# Schematic_EASYEDA.net
KiCad netlist of a schematic drawn in EasyEDA
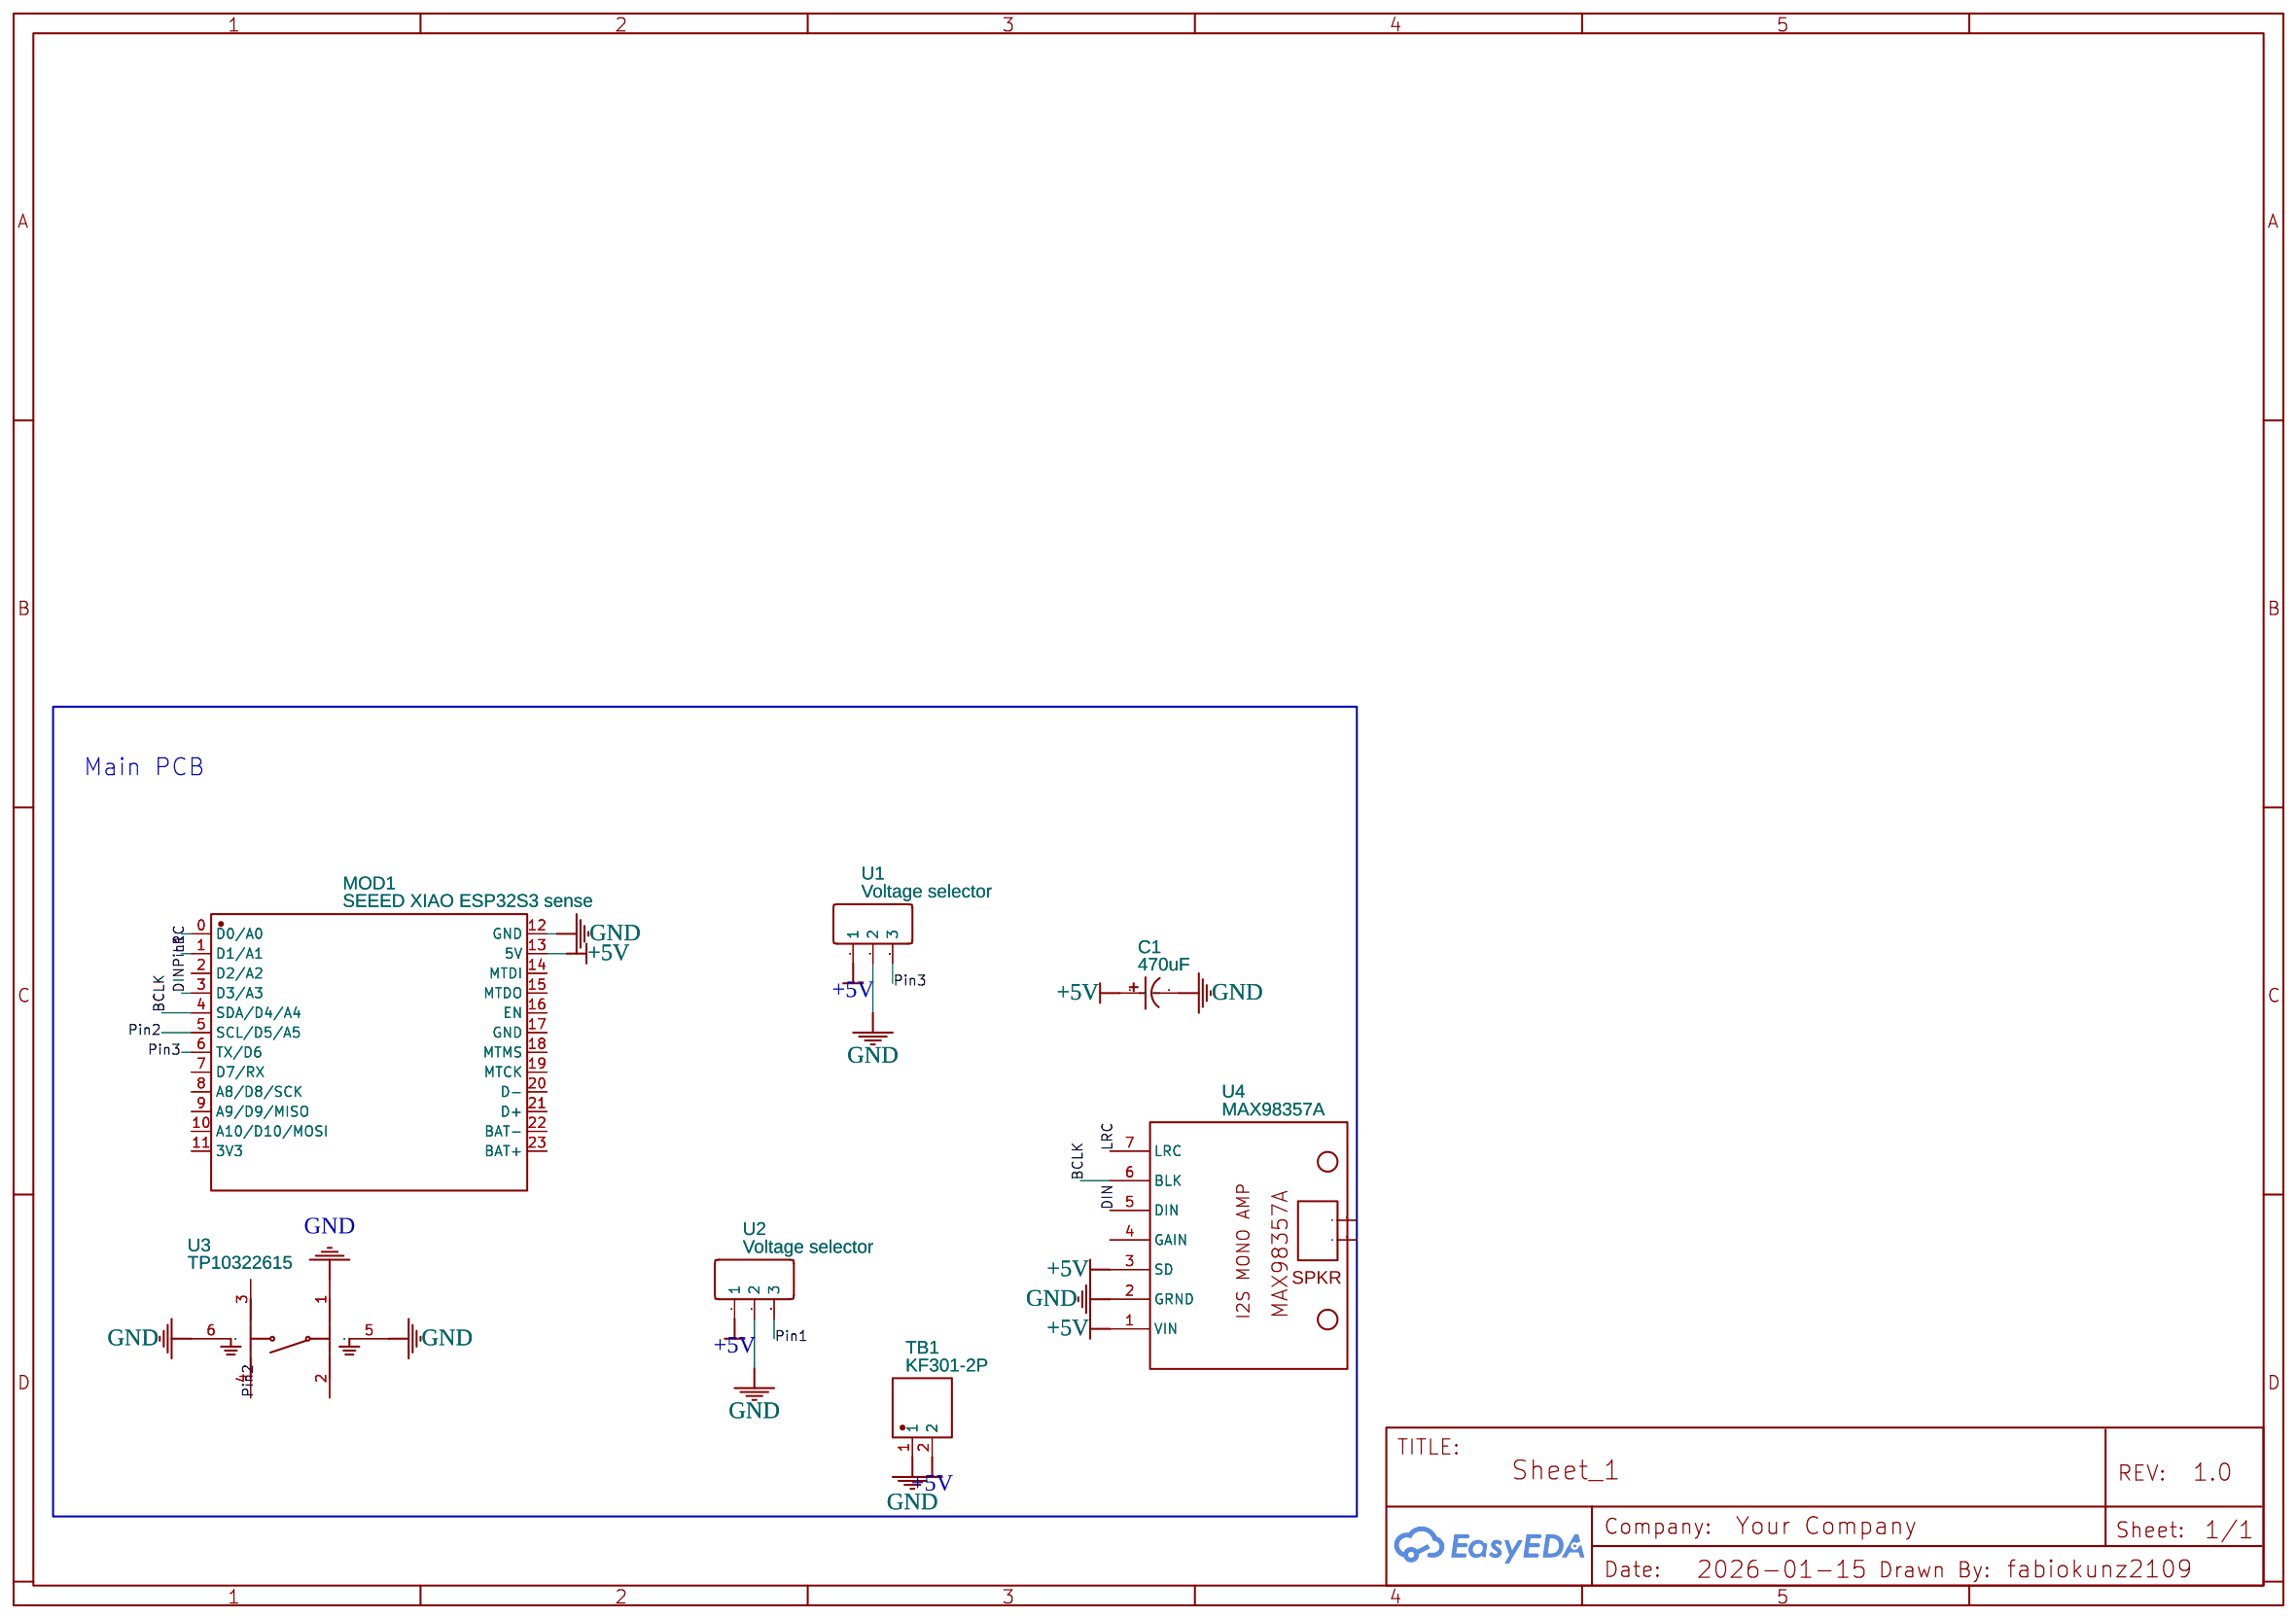
[diagram p0: schematic sheet]

(export (version "E")
  (design (tool "Eeschema 10.0.6"))
  (components
    (comp (ref "C1") (value "470uF") (libsource (lib "") (part "470uF 10V Flat 6.3x12")))
    (comp (ref "MOD1")
      (value "SEEED XIAO ESP32S3 sense")
      (libsource (lib "") (part "SEEED XIAO ESP32S3 sense"))
    )
    (comp (ref "TB1") (value "KF301-2P") (libsource (lib "") (part "KF301-2P")))
    (comp (ref "U1") (value "Voltage selector") (libsource (lib "") (part "Header-Male-2.54-1x3-2-1-Jumper")))
    (comp (ref "U2") (value "Voltage selector") (libsource (lib "") (part "Header-Male-2.54-1x3-2-1-Jumper")))
    (comp (ref "U3")
      (value "TP10322615")
      (fields (field (name "Manufacturer") "ROCPU Switches(台普)"))
      (libsource (lib "") (part "TP10322615"))
    )
    (comp (ref "U4") (value "MAX98357A") (libsource (lib "") (part "MAX98357A COPY")))
  )
  (nets
    (net (code "1") (name "+5V") (class "Default")
      (node (ref "C1") (pin "1") (pinfunction "1_1") (pintype "input"))
      (node (ref "MOD1") (pin "13") (pinfunction "5V_13") (pintype "unspecified"))
      (node (ref "TB1") (pin "2") (pinfunction "2_2") (pintype "unspecified"))
      (node (ref "U1") (pin "1") (pinfunction "1_1") (pintype "unspecified"))
      (node (ref "U2") (pin "1") (pinfunction "1_1") (pintype "unspecified"))
      (node (ref "U4") (pin "1") (pinfunction "VIN_1") (pintype "unspecified"))
      (node (ref "U4") (pin "3") (pinfunction "SD_3") (pintype "unspecified"))
    )
    (net (code "2") (name "/BCLK") (class "Default")
      (node (ref "MOD1") (pin "4") (pinfunction "SDA/D4/A4_4") (pintype "unspecified"))
      (node (ref "U4") (pin "6") (pinfunction "BLK_6") (pintype "unspecified"))
    )
    (net (code "3") (name "/DIN") (class "Default")
      (node (ref "MOD1") (pin "3") (pinfunction "D3/A3_3") (pintype "unspecified"))
      (node (ref "U4") (pin "5") (pinfunction "DIN_5") (pintype "unspecified"))
    )
    (net (code "4") (name "/LRC") (class "Default")
      (node (ref "MOD1") (pin "1") (pinfunction "D1/A1_1") (pintype "unspecified"))
      (node (ref "U4") (pin "7") (pinfunction "LRC_7") (pintype "unspecified"))
    )
    (net (code "5") (name "/Pin1") (class "Default")
      (node (ref "MOD1") (pin "0") (pinfunction "D0/A0_0") (pintype "unspecified"))
      (node (ref "U2") (pin "3") (pinfunction "3_3") (pintype "unspecified"))
    )
    (net (code "6") (name "/Pin2") (class "Default")
      (node (ref "MOD1") (pin "5") (pinfunction "SCL/D5/A5_5") (pintype "unspecified"))
      (node (ref "U3") (pin "4") (pinfunction "4_4") (pintype "unspecified"))
    )
    (net (code "7") (name "/Pin3") (class "Default")
      (node (ref "MOD1") (pin "6") (pinfunction "TX/D6_6") (pintype "unspecified"))
      (node (ref "U1") (pin "3") (pinfunction "3_3") (pintype "unspecified"))
    )
    (net (code "8") (name "GND") (class "Default")
      (node (ref "C1") (pin "2") (pinfunction "2_2") (pintype "input"))
      (node (ref "MOD1") (pin "12") (pinfunction "GND_12") (pintype "unspecified"))
      (node (ref "TB1") (pin "1") (pinfunction "1_1") (pintype "unspecified"))
      (node (ref "U1") (pin "2") (pinfunction "2_2") (pintype "unspecified"))
      (node (ref "U2") (pin "2") (pinfunction "2_2") (pintype "unspecified"))
      (node (ref "U3") (pin "1") (pinfunction "1_1") (pintype "unspecified"))
      (node (ref "U3") (pin "5") (pinfunction "5_5") (pintype "unspecified"))
      (node (ref "U3") (pin "6") (pinfunction "6_6") (pintype "unspecified"))
      (node (ref "U4") (pin "2") (pinfunction "GRND_2") (pintype "unspecified"))
    )
    (net (code "9") (name "unconnected-(MOD1-3V3-Pad11)") (class "Default")
      (node (ref "MOD1") (pin "11") (pinfunction "3V3_11") (pintype "unspecified"))
    )
    (net (code "10") (name "unconnected-(MOD1-A8{slash}D8{slash}SCK-Pad8)") (class "Default")
      (node (ref "MOD1") (pin "8") (pinfunction "A8/D8/SCK_8") (pintype "unspecified"))
    )
    (net (code "11") (name "unconnected-(MOD1-A9{slash}D9{slash}MISO-Pad9)") (class "Default")
      (node (ref "MOD1") (pin "9") (pinfunction "A9/D9/MISO_9") (pintype "unspecified"))
    )
    (net (code "12") (name "unconnected-(MOD1-A10{slash}D10{slash}MOSI-Pad10)") (class "Default")
      (node (ref "MOD1") (pin "10") (pinfunction "A10/D10/MOSI_10") (pintype "unspecified"))
    )
    (net (code "13") (name "unconnected-(MOD1-BAT+-Pad23)") (class "Default")
      (node (ref "MOD1") (pin "23") (pinfunction "BAT+_23") (pintype "unspecified"))
    )
    (net (code "14") (name "unconnected-(MOD1-BAT--Pad22)") (class "Default")
      (node (ref "MOD1") (pin "22") (pinfunction "BAT-_22") (pintype "unspecified"))
    )
    (net (code "15") (name "unconnected-(MOD1-D+-Pad21)") (class "Default")
      (node (ref "MOD1") (pin "21") (pinfunction "D+_21") (pintype "unspecified"))
    )
    (net (code "16") (name "unconnected-(MOD1-D--Pad20)") (class "Default")
      (node (ref "MOD1") (pin "20") (pinfunction "D-_20") (pintype "unspecified"))
    )
    (net (code "17") (name "unconnected-(MOD1-D2{slash}A2-Pad2)") (class "Default")
      (node (ref "MOD1") (pin "2") (pinfunction "D2/A2_2") (pintype "unspecified"))
    )
    (net (code "18") (name "unconnected-(MOD1-D7{slash}RX-Pad7)") (class "Default")
      (node (ref "MOD1") (pin "7") (pinfunction "D7/RX_7") (pintype "unspecified"))
    )
    (net (code "19") (name "unconnected-(MOD1-EN-Pad16)") (class "Default")
      (node (ref "MOD1") (pin "16") (pinfunction "EN_16") (pintype "unspecified"))
    )
    (net (code "20") (name "unconnected-(MOD1-GND-Pad17)") (class "Default")
      (node (ref "MOD1") (pin "17") (pinfunction "GND_17") (pintype "unspecified"))
    )
    (net (code "21") (name "unconnected-(MOD1-MTCK-Pad19)") (class "Default")
      (node (ref "MOD1") (pin "19") (pinfunction "MTCK_19") (pintype "unspecified"))
    )
    (net (code "22") (name "unconnected-(MOD1-MTDI-Pad14)") (class "Default")
      (node (ref "MOD1") (pin "14") (pinfunction "MTDI_14") (pintype "unspecified"))
    )
    (net (code "23") (name "unconnected-(MOD1-MTDO-Pad15)") (class "Default")
      (node (ref "MOD1") (pin "15") (pinfunction "MTDO_15") (pintype "unspecified"))
    )
    (net (code "24") (name "unconnected-(MOD1-MTMS-Pad18)") (class "Default")
      (node (ref "MOD1") (pin "18") (pinfunction "MTMS_18") (pintype "unspecified"))
    )
    (net (code "25") (name "unconnected-(U3-Pad2)") (class "Default")
      (node (ref "U3") (pin "2") (pinfunction "2_2") (pintype "unspecified"))
    )
    (net (code "26") (name "unconnected-(U3-Pad3)") (class "Default")
      (node (ref "U3") (pin "3") (pinfunction "3_3") (pintype "unspecified"))
    )
    (net (code "27") (name "unconnected-(U4-+-Pad1)") (class "Default")
      (node (ref "U4") (pin "1") (pinfunction "+_1") (pintype "unspecified"))
    )
    (net (code "28") (name "unconnected-(U4----Pad2)") (class "Default")
      (node (ref "U4") (pin "2") (pinfunction "--_2") (pintype "unspecified"))
    )
    (net (code "29") (name "unconnected-(U4-GAIN-Pad4)") (class "Default")
      (node (ref "U4") (pin "4") (pinfunction "GAIN_4") (pintype "unspecified"))
    )
  )
)
